# LOGIC_FPGA.net
KiCad netlist of a schematic drawn in Altium Designer
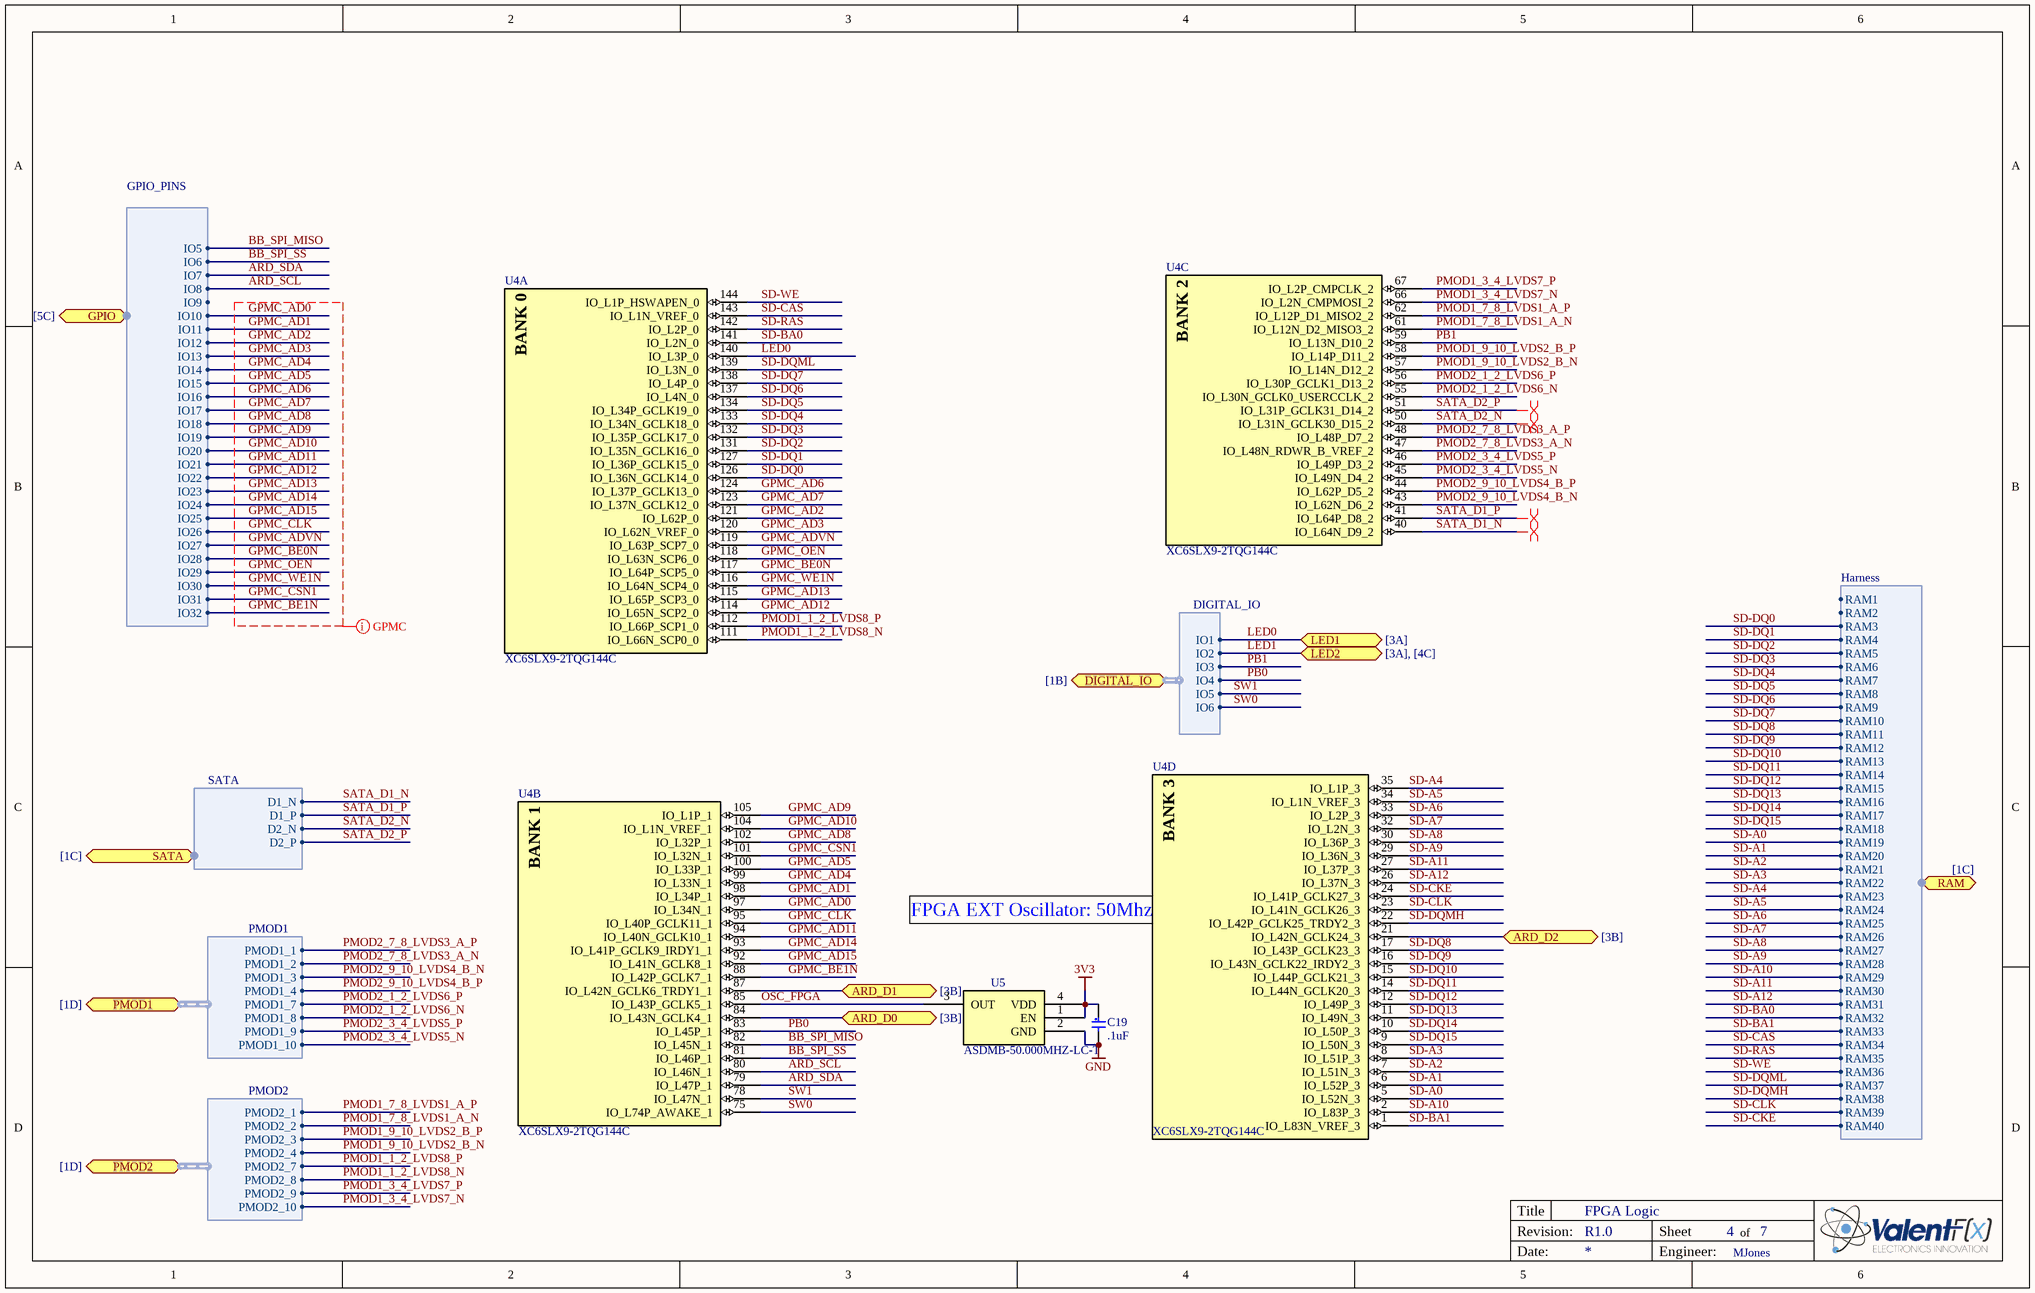
[diagram p0: LOGIC_FPGA.SchDoc]

(export (version "E")
  (design (tool "Eeschema 10.0.6"))
  (components
    (comp (ref "C19")
      (value ".1uF")
      (footprint "c0603")
      (description "CAP CER 0.1UF 25V Y5V 0603")
      (fields
        (field (name "MANUFACTURER") "Samsung Electro-Mechanics America, Inc")
        (field (name "MANUFACTURER PART NUMBER") "CL10F104ZA8NNNC")
      )
      (libsource (lib "mCapacitors") (part "C0603 - CL10F104ZA8NNNC"))
    )
    (comp (ref "U4")
      (value "XC6SLX9-2TQG144C")
      (footprint "TQ144_L")
      (description "IC FPAG SPARTAN 6 9K 144TQFP")
      (fields (field (name "MANUFACTURER") "Xilinx Inc"))
      (libsource (lib "mIC") (part "FPGA - XC6SLX9-2TQG144C"))
    )
    (comp (ref "U5")
      (value "ASDMB-50.000MHZ-LC-T")
      (footprint "ASDMB - osc")
      (description "OSC MEMS 50.000 MHZ SMD")
      (fields (field (name "MANUFACTURER") "Abracon Corporation"))
      (libsource (lib "eIC") (part "ASDMB-50.000MHZ-LC-T"))
    )
  )
  (nets
    (net (code "7") (name "/ARD_D0") (class "Default")
      (node (ref "U4") (pin "84") (pinfunction "IO_L43N_GCLK4_1_84") (pintype "bidirectional"))
    )
    (net (code "8") (name "/ARD_D1") (class "Default")
      (node (ref "U4") (pin "87") (pinfunction "IO_L42N_GCLK6_TRDY1_1_87") (pintype "bidirectional"))
    )
    (net (code "9") (name "/ARD_D2") (class "Default")
      (node (ref "U4") (pin "21") (pinfunction "IO_L42N_GCLK24_3_21") (pintype "bidirectional"))
    )
    (net (code "10") (name "/ARD_SCL") (class "Default")
      (node (ref "U4") (pin "80") (pinfunction "IO_L46N_1_80") (pintype "bidirectional"))
    )
    (net (code "11") (name "/ARD_SDA") (class "Default")
      (node (ref "U4") (pin "79") (pinfunction "IO_L47P_1_79") (pintype "bidirectional"))
    )
    (net (code "12") (name "/BB_SPI_MISO") (class "Default")
      (node (ref "U4") (pin "82") (pinfunction "IO_L45N_1_82") (pintype "bidirectional"))
    )
    (net (code "13") (name "/BB_SPI_SS") (class "Default")
      (node (ref "U4") (pin "81") (pinfunction "IO_L46P_1_81") (pintype "bidirectional"))
    )
    (net (code "14") (name "/GPMC_AD0") (class "Default")
      (node (ref "U4") (pin "97") (pinfunction "IO_L34N_1_97") (pintype "bidirectional"))
    )
    (net (code "15") (name "/GPMC_AD1") (class "Default")
      (node (ref "U4") (pin "98") (pinfunction "IO_L34P_1_98") (pintype "bidirectional"))
    )
    (net (code "16") (name "/GPMC_AD2") (class "Default")
      (node (ref "U4") (pin "121") (pinfunction "IO_L62P_0_121") (pintype "bidirectional"))
    )
    (net (code "17") (name "/GPMC_AD3") (class "Default")
      (node (ref "U4") (pin "120") (pinfunction "IO_L62N_VREF_0_120") (pintype "bidirectional"))
    )
    (net (code "18") (name "/GPMC_AD4") (class "Default")
      (node (ref "U4") (pin "99") (pinfunction "IO_L33N_1_99") (pintype "bidirectional"))
    )
    (net (code "19") (name "/GPMC_AD5") (class "Default")
      (node (ref "U4") (pin "100") (pinfunction "IO_L33P_1_100") (pintype "bidirectional"))
    )
    (net (code "20") (name "/GPMC_AD6") (class "Default")
      (node (ref "U4") (pin "124") (pinfunction "IO_L37P_GCLK13_0_124") (pintype "bidirectional"))
    )
    (net (code "21") (name "/GPMC_AD7") (class "Default")
      (node (ref "U4") (pin "123") (pinfunction "IO_L37N_GCLK12_0_123") (pintype "bidirectional"))
    )
    (net (code "22") (name "/GPMC_AD8") (class "Default")
      (node (ref "U4") (pin "102") (pinfunction "IO_L32P_1_102") (pintype "bidirectional"))
    )
    (net (code "23") (name "/GPMC_AD9") (class "Default")
      (node (ref "U4") (pin "105") (pinfunction "IO_L1P_1_105") (pintype "bidirectional"))
    )
    (net (code "24") (name "/GPMC_AD10") (class "Default")
      (node (ref "U4") (pin "104") (pinfunction "IO_L1N_VREF_1_104") (pintype "bidirectional"))
    )
    (net (code "25") (name "/GPMC_AD11") (class "Default")
      (node (ref "U4") (pin "94") (pinfunction "IO_L40N_GCLK10_1_94") (pintype "bidirectional"))
    )
    (net (code "26") (name "/GPMC_AD12") (class "Default")
      (node (ref "U4") (pin "114") (pinfunction "IO_L65N_SCP2_0_114") (pintype "bidirectional"))
    )
    (net (code "27") (name "/GPMC_AD13") (class "Default")
      (node (ref "U4") (pin "115") (pinfunction "IO_L65P_SCP3_0_115") (pintype "bidirectional"))
    )
    (net (code "28") (name "/GPMC_AD14") (class "Default")
      (node (ref "U4") (pin "93") (pinfunction "IO_L41P_GCLK9_IRDY1_1_93") (pintype "bidirectional"))
    )
    (net (code "29") (name "/GPMC_AD15") (class "Default")
      (node (ref "U4") (pin "92") (pinfunction "IO_L41N_GCLK8_1_92") (pintype "bidirectional"))
    )
    (net (code "30") (name "/GPMC_ADVN") (class "Default")
      (node (ref "U4") (pin "119") (pinfunction "IO_L63P_SCP7_0_119") (pintype "bidirectional"))
    )
    (net (code "31") (name "/GPMC_BE0N") (class "Default")
      (node (ref "U4") (pin "117") (pinfunction "IO_L64P_SCP5_0_117") (pintype "bidirectional"))
    )
    (net (code "32") (name "/GPMC_BE1N") (class "Default")
      (node (ref "U4") (pin "88") (pinfunction "IO_L42P_GCLK7_1_88") (pintype "bidirectional"))
    )
    (net (code "33") (name "/GPMC_CLK") (class "Default")
      (node (ref "U4") (pin "95") (pinfunction "IO_L40P_GCLK11_1_95") (pintype "bidirectional"))
    )
    (net (code "34") (name "/GPMC_CSN1") (class "Default")
      (node (ref "U4") (pin "101") (pinfunction "IO_L32N_1_101") (pintype "bidirectional"))
    )
    (net (code "35") (name "/GPMC_OEN") (class "Default")
      (node (ref "U4") (pin "118") (pinfunction "IO_L63N_SCP6_0_118") (pintype "bidirectional"))
    )
    (net (code "36") (name "/GPMC_WE1N") (class "Default")
      (node (ref "U4") (pin "116") (pinfunction "IO_L64N_SCP4_0_116") (pintype "bidirectional"))
    )
    (net (code "37") (name "/LED0") (class "Default")
      (node (ref "U4") (pin "140") (pinfunction "IO_L3P_0_140") (pintype "bidirectional"))
    )
    (net (code "38") (name "/OSC_FPGA") (class "Default")
      (node (ref "U4") (pin "85") (pinfunction "IO_L43P_GCLK5_1_85") (pintype "bidirectional"))
      (node (ref "U5") (pin "3") (pinfunction "OUT_3") (pintype "passive"))
    )
    (net (code "39") (name "/PB0") (class "Default")
      (node (ref "U4") (pin "83") (pinfunction "IO_L45P_1_83") (pintype "bidirectional"))
    )
    (net (code "40") (name "/PB1") (class "Default")
      (node (ref "U4") (pin "59") (pinfunction "IO_L13N_D10_2_59") (pintype "bidirectional"))
    )
    (net (code "41") (name "/PMOD1_1_2_LVDS8_N") (class "Default")
      (node (ref "U4") (pin "111") (pinfunction "IO_L66N_SCP0_0_111") (pintype "bidirectional"))
    )
    (net (code "42") (name "/PMOD1_1_2_LVDS8_P") (class "Default")
      (node (ref "U4") (pin "112") (pinfunction "IO_L66P_SCP1_0_112") (pintype "bidirectional"))
    )
    (net (code "43") (name "/PMOD1_3_4_LVDS7_N") (class "Default")
      (node (ref "U4") (pin "66") (pinfunction "IO_L2N_CMPMOSI_2_66") (pintype "bidirectional"))
    )
    (net (code "44") (name "/PMOD1_3_4_LVDS7_P") (class "Default")
      (node (ref "U4") (pin "67") (pinfunction "IO_L2P_CMPCLK_2_67") (pintype "bidirectional"))
    )
    (net (code "45") (name "/PMOD1_7_8_LVDS1_A_N") (class "Default")
      (node (ref "U4") (pin "61") (pinfunction "IO_L12N_D2_MISO3_2_61") (pintype "bidirectional"))
    )
    (net (code "46") (name "/PMOD1_7_8_LVDS1_A_P") (class "Default")
      (node (ref "U4") (pin "62") (pinfunction "IO_L12P_D1_MISO2_2_62") (pintype "bidirectional"))
    )
    (net (code "47") (name "/PMOD1_9_10_LVDS2_B_N") (class "Default")
      (node (ref "U4") (pin "57") (pinfunction "IO_L14N_D12_2_57") (pintype "bidirectional"))
    )
    (net (code "48") (name "/PMOD1_9_10_LVDS2_B_P") (class "Default")
      (node (ref "U4") (pin "58") (pinfunction "IO_L14P_D11_2_58") (pintype "bidirectional"))
    )
    (net (code "49") (name "/PMOD2_1_2_LVDS6_N") (class "Default")
      (node (ref "U4") (pin "55") (pinfunction "IO_L30N_GCLK0_USERCCLK_2_55") (pintype "bidirectional"))
    )
    (net (code "50") (name "/PMOD2_1_2_LVDS6_P") (class "Default")
      (node (ref "U4") (pin "56") (pinfunction "IO_L30P_GCLK1_D13_2_56") (pintype "bidirectional"))
    )
    (net (code "51") (name "/PMOD2_3_4_LVDS5_N") (class "Default")
      (node (ref "U4") (pin "45") (pinfunction "IO_L49N_D4_2_45") (pintype "bidirectional"))
    )
    (net (code "52") (name "/PMOD2_3_4_LVDS5_P") (class "Default")
      (node (ref "U4") (pin "46") (pinfunction "IO_L49P_D3_2_46") (pintype "bidirectional"))
    )
    (net (code "53") (name "/PMOD2_7_8_LVDS3_A_N") (class "Default")
      (node (ref "U4") (pin "47") (pinfunction "IO_L48N_RDWR_B_VREF_2_47") (pintype "bidirectional"))
    )
    (net (code "54") (name "/PMOD2_7_8_LVDS3_A_P") (class "Default")
      (node (ref "U4") (pin "48") (pinfunction "IO_L48P_D7_2_48") (pintype "bidirectional"))
    )
    (net (code "55") (name "/PMOD2_9_10_LVDS4_B_N") (class "Default")
      (node (ref "U4") (pin "43") (pinfunction "IO_L62N_D6_2_43") (pintype "bidirectional"))
    )
    (net (code "56") (name "/PMOD2_9_10_LVDS4_B_P") (class "Default")
      (node (ref "U4") (pin "44") (pinfunction "IO_L62P_D5_2_44") (pintype "bidirectional"))
    )
    (net (code "57") (name "/SATA_D1_N") (class "Default")
      (node (ref "U4") (pin "40") (pinfunction "IO_L64N_D9_2_40") (pintype "bidirectional"))
    )
    (net (code "58") (name "/SATA_D1_P") (class "Default")
      (node (ref "U4") (pin "41") (pinfunction "IO_L64P_D8_2_41") (pintype "bidirectional"))
    )
    (net (code "59") (name "/SATA_D2_N") (class "Default")
      (node (ref "U4") (pin "50") (pinfunction "IO_L31N_GCLK30_D15_2_50") (pintype "bidirectional"))
    )
    (net (code "60") (name "/SATA_D2_P") (class "Default")
      (node (ref "U4") (pin "51") (pinfunction "IO_L31P_GCLK31_D14_2_51") (pintype "bidirectional"))
    )
    (net (code "61") (name "/SD-A0") (class "Default")
      (node (ref "U4") (pin "5") (pinfunction "IO_L52N_3_5") (pintype "bidirectional"))
    )
    (net (code "62") (name "/SD-A1") (class "Default")
      (node (ref "U4") (pin "6") (pinfunction "IO_L52P_3_6") (pintype "bidirectional"))
    )
    (net (code "63") (name "/SD-A2") (class "Default")
      (node (ref "U4") (pin "7") (pinfunction "IO_L51N_3_7") (pintype "bidirectional"))
    )
    (net (code "64") (name "/SD-A3") (class "Default")
      (node (ref "U4") (pin "8") (pinfunction "IO_L51P_3_8") (pintype "bidirectional"))
    )
    (net (code "65") (name "/SD-A4") (class "Default")
      (node (ref "U4") (pin "35") (pinfunction "IO_L1P_3_35") (pintype "bidirectional"))
    )
    (net (code "66") (name "/SD-A5") (class "Default")
      (node (ref "U4") (pin "34") (pinfunction "IO_L1N_VREF_3_34") (pintype "bidirectional"))
    )
    (net (code "67") (name "/SD-A6") (class "Default")
      (node (ref "U4") (pin "33") (pinfunction "IO_L2P_3_33") (pintype "bidirectional"))
    )
    (net (code "68") (name "/SD-A7") (class "Default")
      (node (ref "U4") (pin "32") (pinfunction "IO_L2N_3_32") (pintype "bidirectional"))
    )
    (net (code "69") (name "/SD-A8") (class "Default")
      (node (ref "U4") (pin "30") (pinfunction "IO_L36P_3_30") (pintype "bidirectional"))
    )
    (net (code "70") (name "/SD-A9") (class "Default")
      (node (ref "U4") (pin "29") (pinfunction "IO_L36N_3_29") (pintype "bidirectional"))
    )
    (net (code "71") (name "/SD-A10") (class "Default")
      (node (ref "U4") (pin "2") (pinfunction "IO_L83P_3_2") (pintype "bidirectional"))
    )
    (net (code "72") (name "/SD-A11") (class "Default")
      (node (ref "U4") (pin "27") (pinfunction "IO_L37P_3_27") (pintype "bidirectional"))
    )
    (net (code "73") (name "/SD-A12") (class "Default")
      (node (ref "U4") (pin "26") (pinfunction "IO_L37N_3_26") (pintype "bidirectional"))
    )
    (net (code "74") (name "/SD-BA0") (class "Default")
      (node (ref "U4") (pin "141") (pinfunction "IO_L2N_0_141") (pintype "bidirectional"))
    )
    (net (code "75") (name "/SD-BA1") (class "Default")
      (node (ref "U4") (pin "1") (pinfunction "IO_L83N_VREF_3_1") (pintype "bidirectional"))
    )
    (net (code "76") (name "/SD-CAS") (class "Default")
      (node (ref "U4") (pin "143") (pinfunction "IO_L1N_VREF_0_143") (pintype "bidirectional"))
    )
    (net (code "77") (name "/SD-CKE") (class "Default")
      (node (ref "U4") (pin "24") (pinfunction "IO_L41P_GCLK27_3_24") (pintype "bidirectional"))
    )
    (net (code "78") (name "/SD-CLK") (class "Default")
      (node (ref "U4") (pin "23") (pinfunction "IO_L41N_GCLK26_3_23") (pintype "bidirectional"))
    )
    (net (code "79") (name "/SD-DQ0") (class "Default")
      (node (ref "U4") (pin "126") (pinfunction "IO_L36N_GCLK14_0_126") (pintype "bidirectional"))
    )
    (net (code "80") (name "/SD-DQ1") (class "Default")
      (node (ref "U4") (pin "127") (pinfunction "IO_L36P_GCLK15_0_127") (pintype "bidirectional"))
    )
    (net (code "81") (name "/SD-DQ2") (class "Default")
      (node (ref "U4") (pin "131") (pinfunction "IO_L35N_GCLK16_0_131") (pintype "bidirectional"))
    )
    (net (code "82") (name "/SD-DQ3") (class "Default")
      (node (ref "U4") (pin "132") (pinfunction "IO_L35P_GCLK17_0_132") (pintype "bidirectional"))
    )
    (net (code "83") (name "/SD-DQ4") (class "Default")
      (node (ref "U4") (pin "133") (pinfunction "IO_L34N_GCLK18_0_133") (pintype "bidirectional"))
    )
    (net (code "84") (name "/SD-DQ5") (class "Default")
      (node (ref "U4") (pin "134") (pinfunction "IO_L34P_GCLK19_0_134") (pintype "bidirectional"))
    )
    (net (code "85") (name "/SD-DQ6") (class "Default")
      (node (ref "U4") (pin "137") (pinfunction "IO_L4N_0_137") (pintype "bidirectional"))
    )
    (net (code "86") (name "/SD-DQ7") (class "Default")
      (node (ref "U4") (pin "138") (pinfunction "IO_L4P_0_138") (pintype "bidirectional"))
    )
    (net (code "87") (name "/SD-DQ8") (class "Default")
      (node (ref "U4") (pin "17") (pinfunction "IO_L43P_GCLK23_3_17") (pintype "bidirectional"))
    )
    (net (code "88") (name "/SD-DQ9") (class "Default")
      (node (ref "U4") (pin "16") (pinfunction "IO_L43N_GCLK22_IRDY2_3_16") (pintype "bidirectional"))
    )
    (net (code "89") (name "/SD-DQ10") (class "Default")
      (node (ref "U4") (pin "15") (pinfunction "IO_L44P_GCLK21_3_15") (pintype "bidirectional"))
    )
    (net (code "90") (name "/SD-DQ11") (class "Default")
      (node (ref "U4") (pin "14") (pinfunction "IO_L44N_GCLK20_3_14") (pintype "bidirectional"))
    )
    (net (code "91") (name "/SD-DQ12") (class "Default")
      (node (ref "U4") (pin "12") (pinfunction "IO_L49P_3_12") (pintype "bidirectional"))
    )
    (net (code "92") (name "/SD-DQ13") (class "Default")
      (node (ref "U4") (pin "11") (pinfunction "IO_L49N_3_11") (pintype "bidirectional"))
    )
    (net (code "93") (name "/SD-DQ14") (class "Default")
      (node (ref "U4") (pin "10") (pinfunction "IO_L50P_3_10") (pintype "bidirectional"))
    )
    (net (code "94") (name "/SD-DQ15") (class "Default")
      (node (ref "U4") (pin "9") (pinfunction "IO_L50N_3_9") (pintype "bidirectional"))
    )
    (net (code "95") (name "/SD-DQMH") (class "Default")
      (node (ref "U4") (pin "22") (pinfunction "IO_L42P_GCLK25_TRDY2_3_22") (pintype "bidirectional"))
    )
    (net (code "96") (name "/SD-DQML") (class "Default")
      (node (ref "U4") (pin "139") (pinfunction "IO_L3N_0_139") (pintype "bidirectional"))
    )
    (net (code "97") (name "/SD-RAS") (class "Default")
      (node (ref "U4") (pin "142") (pinfunction "IO_L2P_0_142") (pintype "bidirectional"))
    )
    (net (code "98") (name "/SD-WE") (class "Default")
      (node (ref "U4") (pin "144") (pinfunction "IO_L1P_HSWAPEN_0_144") (pintype "bidirectional"))
    )
    (net (code "99") (name "/SW0") (class "Default")
      (node (ref "U4") (pin "75") (pinfunction "IO_L74P_AWAKE_1_75") (pintype "bidirectional"))
    )
    (net (code "100") (name "/SW1") (class "Default")
      (node (ref "U4") (pin "78") (pinfunction "IO_L47N_1_78") (pintype "bidirectional"))
    )
    (net (code "107") (name "3V3") (class "Default")
      (node (ref "C19") (pin "1") (pinfunction "1_1") (pintype "passive"))
      (node (ref "U5") (pin "1") (pinfunction "EN_1") (pintype "passive"))
      (node (ref "U5") (pin "4") (pinfunction "VDD_4") (pintype "passive"))
    )
    (net (code "108") (name "GND") (class "Default")
      (node (ref "C19") (pin "2") (pinfunction "2_2") (pintype "passive"))
      (node (ref "U5") (pin "2") (pinfunction "GND_2") (pintype "passive"))
    )
  )
)
